# aop.net
KiCad netlist of a schematic drawn in EAGLE
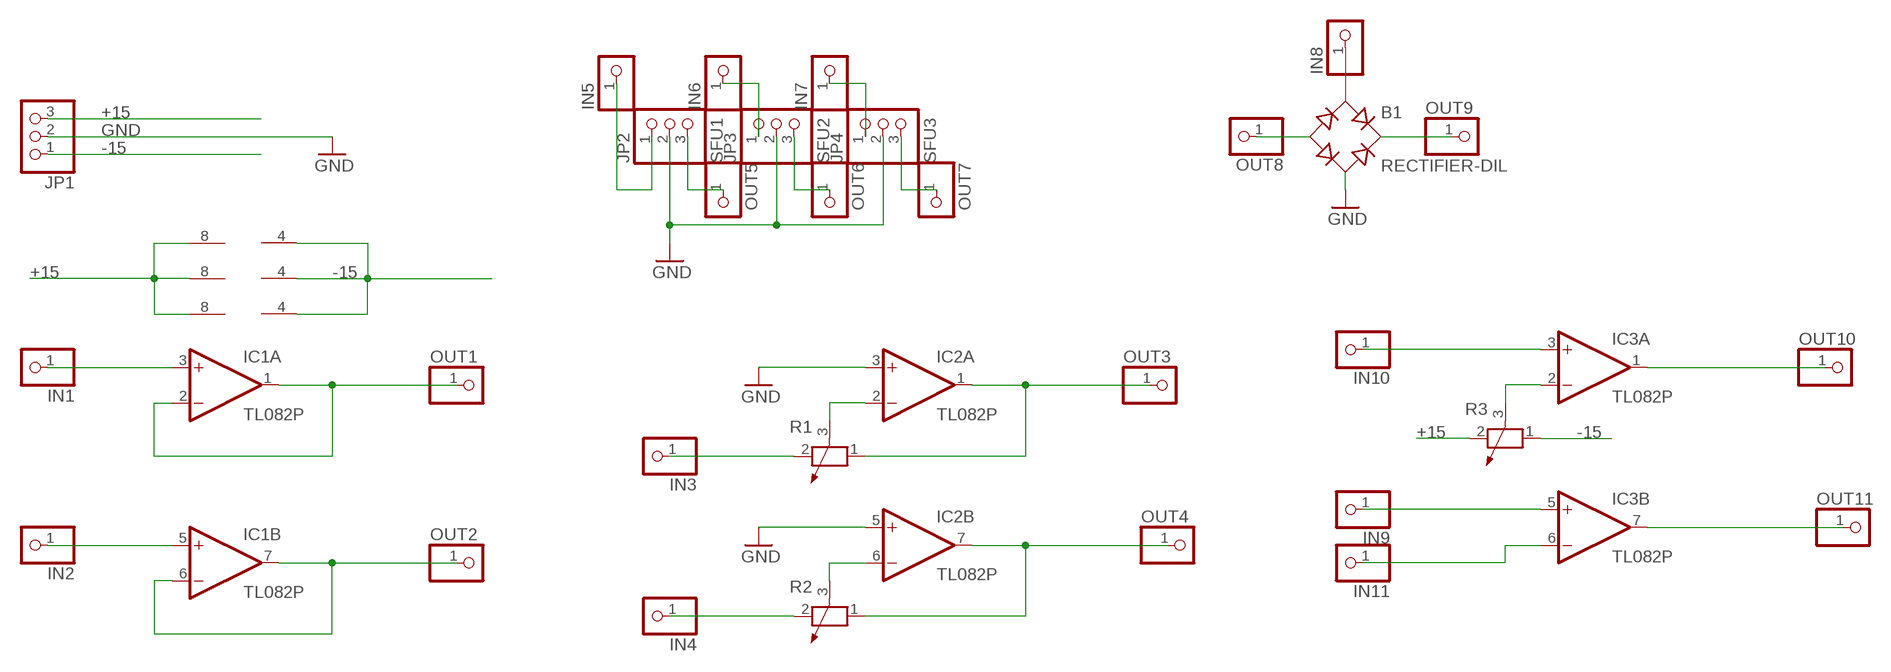
[diagram p0: schematic, sheet 1]

(export (version "E")
  (design (tool "Eeschema 10.0.6"))
  (components
    (comp (ref "B1")
      (value "RECTIFIER-DIL")
      (footprint "eagle-import:B-DIL")
      (libsource (lib "eagle-import") (part "RECTIFIER-DIL"))
    )
    (comp (ref "IC1")
      (value "TL082P")
      (footprint "eagle-import:DIL08")
      (libsource (lib "eagle-import") (part "TL082P"))
    )
    (comp (ref "IC2")
      (value "TL082P")
      (footprint "eagle-import:DIL08")
      (libsource (lib "eagle-import") (part "TL082P"))
    )
    (comp (ref "IC3")
      (value "TL082P")
      (footprint "eagle-import:DIL08")
      (libsource (lib "eagle-import") (part "TL082P"))
    )
    (comp (ref "IN1")
      (value "PINHD-1X1")
      (footprint "eagle-import:1X01")
      (libsource (lib "eagle-import") (part "PINHD-1X1"))
    )
    (comp (ref "IN2")
      (value "PINHD-1X1")
      (footprint "eagle-import:1X01")
      (libsource (lib "eagle-import") (part "PINHD-1X1"))
    )
    (comp (ref "IN3")
      (value "PINHD-1X1")
      (footprint "eagle-import:1X01")
      (libsource (lib "eagle-import") (part "PINHD-1X1"))
    )
    (comp (ref "IN4")
      (value "PINHD-1X1")
      (footprint "eagle-import:1X01")
      (libsource (lib "eagle-import") (part "PINHD-1X1"))
    )
    (comp (ref "IN5")
      (value "PINHD-1X1")
      (footprint "eagle-import:1X01")
      (libsource (lib "eagle-import") (part "PINHD-1X1"))
    )
    (comp (ref "IN6")
      (value "PINHD-1X1")
      (footprint "eagle-import:1X01")
      (libsource (lib "eagle-import") (part "PINHD-1X1"))
    )
    (comp (ref "IN7")
      (value "PINHD-1X1")
      (footprint "eagle-import:1X01")
      (libsource (lib "eagle-import") (part "PINHD-1X1"))
    )
    (comp (ref "IN8")
      (value "PINHD-1X1")
      (footprint "eagle-import:1X01")
      (libsource (lib "eagle-import") (part "PINHD-1X1"))
    )
    (comp (ref "IN9")
      (value "PINHD-1X1")
      (footprint "eagle-import:1X01")
      (libsource (lib "eagle-import") (part "PINHD-1X1"))
    )
    (comp (ref "IN10")
      (value "PINHD-1X1")
      (footprint "eagle-import:1X01")
      (libsource (lib "eagle-import") (part "PINHD-1X1"))
    )
    (comp (ref "IN11")
      (value "PINHD-1X1")
      (footprint "eagle-import:1X01")
      (libsource (lib "eagle-import") (part "PINHD-1X1"))
    )
    (comp (ref "JP1")
      (value "PINHD-1X3")
      (footprint "eagle-import:1X03")
      (libsource (lib "eagle-import") (part "PINHD-1X3"))
    )
    (comp (ref "JP2")
      (value "SFU1")
      (footprint "eagle-import:1X03")
      (libsource (lib "eagle-import") (part "PINHD-1X3"))
    )
    (comp (ref "JP3")
      (value "SFU2")
      (footprint "eagle-import:1X03")
      (libsource (lib "eagle-import") (part "PINHD-1X3"))
    )
    (comp (ref "JP4")
      (value "SFU3")
      (footprint "eagle-import:1X03")
      (libsource (lib "eagle-import") (part "PINHD-1X3"))
    )
    (comp (ref "OUT1")
      (value "PINHD-1X1")
      (footprint "eagle-import:1X01")
      (libsource (lib "eagle-import") (part "PINHD-1X1"))
    )
    (comp (ref "OUT2")
      (value "PINHD-1X1")
      (footprint "eagle-import:1X01")
      (libsource (lib "eagle-import") (part "PINHD-1X1"))
    )
    (comp (ref "OUT3")
      (value "PINHD-1X1")
      (footprint "eagle-import:1X01")
      (libsource (lib "eagle-import") (part "PINHD-1X1"))
    )
    (comp (ref "OUT4")
      (value "PINHD-1X1")
      (footprint "eagle-import:1X01")
      (libsource (lib "eagle-import") (part "PINHD-1X1"))
    )
    (comp (ref "OUT5")
      (value "PINHD-1X1")
      (footprint "eagle-import:1X01")
      (libsource (lib "eagle-import") (part "PINHD-1X1"))
    )
    (comp (ref "OUT6")
      (value "PINHD-1X1")
      (footprint "eagle-import:1X01")
      (libsource (lib "eagle-import") (part "PINHD-1X1"))
    )
    (comp (ref "OUT7")
      (value "PINHD-1X1")
      (footprint "eagle-import:1X01")
      (libsource (lib "eagle-import") (part "PINHD-1X1"))
    )
    (comp (ref "OUT8")
      (value "PINHD-1X1")
      (footprint "eagle-import:1X01")
      (libsource (lib "eagle-import") (part "PINHD-1X1"))
    )
    (comp (ref "OUT9")
      (value "PINHD-1X1")
      (footprint "eagle-import:1X01")
      (libsource (lib "eagle-import") (part "PINHD-1X1"))
    )
    (comp (ref "OUT10")
      (value "PINHD-1X1")
      (footprint "eagle-import:1X01")
      (libsource (lib "eagle-import") (part "PINHD-1X1"))
    )
    (comp (ref "OUT11")
      (value "PINHD-1X1")
      (footprint "eagle-import:1X01")
      (libsource (lib "eagle-import") (part "PINHD-1X1"))
    )
    (comp (ref "R1")
      (value "POTENTIOMETER_PT-10")
      (footprint "eagle-import:PT-10")
      (libsource (lib "eagle-import") (part "POTENTIOMETER_PT-10"))
    )
    (comp (ref "R2")
      (value "POTENTIOMETER_PT-10")
      (footprint "eagle-import:PT-10")
      (libsource (lib "eagle-import") (part "POTENTIOMETER_PT-10"))
    )
    (comp (ref "R3")
      (value "POTENTIOMETER_PT-10")
      (footprint "eagle-import:PT-10")
      (libsource (lib "eagle-import") (part "POTENTIOMETER_PT-10"))
    )
  )
  (nets
    (net (code "1") (name "/+15") (class "Default")
      (node (ref "IC1") (pin "8") (pinfunction "V+_8") (pintype "power_in"))
      (node (ref "IC2") (pin "8") (pinfunction "V+_8") (pintype "power_in"))
      (node (ref "IC3") (pin "8") (pinfunction "V+_8") (pintype "power_in"))
      (node (ref "JP1") (pin "3") (pinfunction "3_3") (pintype "passive"))
      (node (ref "R3") (pin "2") (pinfunction "2_2") (pintype "passive"))
    )
    (net (code "2") (name "/-15") (class "Default")
      (node (ref "IC1") (pin "4") (pinfunction "V-_4") (pintype "power_in"))
      (node (ref "IC2") (pin "4") (pinfunction "V-_4") (pintype "power_in"))
      (node (ref "IC3") (pin "4") (pinfunction "V-_4") (pintype "power_in"))
      (node (ref "JP1") (pin "1") (pinfunction "1_1") (pintype "passive"))
      (node (ref "R3") (pin "1") (pinfunction "1_1") (pintype "passive"))
    )
    (net (code "3") (name "GND") (class "Default")
      (node (ref "B1") (pin "AC2") (pinfunction "AC2_AC2") (pintype "passive"))
      (node (ref "IC2") (pin "3") (pinfunction "+IN_3") (pintype "input"))
      (node (ref "IC2") (pin "5") (pinfunction "+IN_5") (pintype "input"))
      (node (ref "JP1") (pin "2") (pinfunction "2_2") (pintype "passive"))
      (node (ref "JP2") (pin "2") (pinfunction "2_2") (pintype "passive"))
      (node (ref "JP3") (pin "2") (pinfunction "2_2") (pintype "passive"))
      (node (ref "JP4") (pin "2") (pinfunction "2_2") (pintype "passive"))
    )
    (net (code "4") (name "Net-(B1-Pad+)") (class "Default")
      (node (ref "B1") (pin "+") (pinfunction "+_+") (pintype "passive"))
      (node (ref "OUT9") (pin "1") (pinfunction "1_1") (pintype "passive"))
    )
    (net (code "5") (name "Net-(B1-Pad-)") (class "Default")
      (node (ref "B1") (pin "-") (pinfunction "-_-") (pintype "passive"))
      (node (ref "OUT8") (pin "1") (pinfunction "1_1") (pintype "passive"))
    )
    (net (code "6") (name "Net-(B1-PadAC1)") (class "Default")
      (node (ref "B1") (pin "AC1") (pinfunction "AC1_AC1") (pintype "passive"))
      (node (ref "IN8") (pin "1") (pinfunction "1_1") (pintype "passive"))
    )
    (net (code "7") (name "Net-(IC1A-+IN)") (class "Default")
      (node (ref "IC1") (pin "3") (pinfunction "+IN_3") (pintype "input"))
      (node (ref "IN1") (pin "1") (pinfunction "1_1") (pintype "passive"))
    )
    (net (code "8") (name "Net-(IC1A--IN)") (class "Default")
      (node (ref "IC1") (pin "1") (pinfunction "OUT_1") (pintype "output"))
      (node (ref "IC1") (pin "2") (pinfunction "-IN_2") (pintype "input"))
      (node (ref "OUT1") (pin "1") (pinfunction "1_1") (pintype "passive"))
    )
    (net (code "9") (name "Net-(IC1B-+IN)") (class "Default")
      (node (ref "IC1") (pin "5") (pinfunction "+IN_5") (pintype "input"))
      (node (ref "IN2") (pin "1") (pinfunction "1_1") (pintype "passive"))
    )
    (net (code "10") (name "Net-(IC1B--IN)") (class "Default")
      (node (ref "IC1") (pin "6") (pinfunction "-IN_6") (pintype "input"))
      (node (ref "IC1") (pin "7") (pinfunction "OUT_7") (pintype "output"))
      (node (ref "OUT2") (pin "1") (pinfunction "1_1") (pintype "passive"))
    )
    (net (code "11") (name "Net-(IC2A--IN)") (class "Default")
      (node (ref "IC2") (pin "2") (pinfunction "-IN_2") (pintype "input"))
      (node (ref "R1") (pin "3") (pinfunction "3_3") (pintype "passive"))
    )
    (net (code "12") (name "Net-(IC2A-OUT)") (class "Default")
      (node (ref "IC2") (pin "1") (pinfunction "OUT_1") (pintype "output"))
      (node (ref "OUT3") (pin "1") (pinfunction "1_1") (pintype "passive"))
      (node (ref "R1") (pin "1") (pinfunction "1_1") (pintype "passive"))
    )
    (net (code "13") (name "Net-(IC2B--IN)") (class "Default")
      (node (ref "IC2") (pin "6") (pinfunction "-IN_6") (pintype "input"))
      (node (ref "R2") (pin "3") (pinfunction "3_3") (pintype "passive"))
    )
    (net (code "14") (name "Net-(IC2B-OUT)") (class "Default")
      (node (ref "IC2") (pin "7") (pinfunction "OUT_7") (pintype "output"))
      (node (ref "OUT4") (pin "1") (pinfunction "1_1") (pintype "passive"))
      (node (ref "R2") (pin "1") (pinfunction "1_1") (pintype "passive"))
    )
    (net (code "15") (name "Net-(IC3A-+IN)") (class "Default")
      (node (ref "IC3") (pin "3") (pinfunction "+IN_3") (pintype "input"))
      (node (ref "IN10") (pin "1") (pinfunction "1_1") (pintype "passive"))
    )
    (net (code "16") (name "Net-(IC3A--IN)") (class "Default")
      (node (ref "IC3") (pin "2") (pinfunction "-IN_2") (pintype "input"))
      (node (ref "R3") (pin "3") (pinfunction "3_3") (pintype "passive"))
    )
    (net (code "17") (name "Net-(IC3A-OUT)") (class "Default")
      (node (ref "IC3") (pin "1") (pinfunction "OUT_1") (pintype "output"))
      (node (ref "OUT10") (pin "1") (pinfunction "1_1") (pintype "passive"))
    )
    (net (code "18") (name "Net-(IC3B-+IN)") (class "Default")
      (node (ref "IC3") (pin "5") (pinfunction "+IN_5") (pintype "input"))
      (node (ref "IN9") (pin "1") (pinfunction "1_1") (pintype "passive"))
    )
    (net (code "19") (name "Net-(IC3B--IN)") (class "Default")
      (node (ref "IC3") (pin "6") (pinfunction "-IN_6") (pintype "input"))
      (node (ref "IN11") (pin "1") (pinfunction "1_1") (pintype "passive"))
    )
    (net (code "20") (name "Net-(IC3B-OUT)") (class "Default")
      (node (ref "IC3") (pin "7") (pinfunction "OUT_7") (pintype "output"))
      (node (ref "OUT11") (pin "1") (pinfunction "1_1") (pintype "passive"))
    )
    (net (code "21") (name "Net-(IN3-Pad1)") (class "Default")
      (node (ref "IN3") (pin "1") (pinfunction "1_1") (pintype "passive"))
      (node (ref "R1") (pin "2") (pinfunction "2_2") (pintype "passive"))
    )
    (net (code "22") (name "Net-(IN4-Pad1)") (class "Default")
      (node (ref "IN4") (pin "1") (pinfunction "1_1") (pintype "passive"))
      (node (ref "R2") (pin "2") (pinfunction "2_2") (pintype "passive"))
    )
    (net (code "23") (name "Net-(IN5-Pad1)") (class "Default")
      (node (ref "IN5") (pin "1") (pinfunction "1_1") (pintype "passive"))
      (node (ref "JP2") (pin "1") (pinfunction "1_1") (pintype "passive"))
    )
    (net (code "24") (name "Net-(IN6-Pad1)") (class "Default")
      (node (ref "IN6") (pin "1") (pinfunction "1_1") (pintype "passive"))
      (node (ref "JP3") (pin "1") (pinfunction "1_1") (pintype "passive"))
    )
    (net (code "25") (name "Net-(IN7-Pad1)") (class "Default")
      (node (ref "IN7") (pin "1") (pinfunction "1_1") (pintype "passive"))
      (node (ref "JP4") (pin "1") (pinfunction "1_1") (pintype "passive"))
    )
    (net (code "26") (name "Net-(JP2-Pad3)") (class "Default")
      (node (ref "JP2") (pin "3") (pinfunction "3_3") (pintype "passive"))
      (node (ref "OUT5") (pin "1") (pinfunction "1_1") (pintype "passive"))
    )
    (net (code "27") (name "Net-(JP3-Pad3)") (class "Default")
      (node (ref "JP3") (pin "3") (pinfunction "3_3") (pintype "passive"))
      (node (ref "OUT6") (pin "1") (pinfunction "1_1") (pintype "passive"))
    )
    (net (code "28") (name "Net-(JP4-Pad3)") (class "Default")
      (node (ref "JP4") (pin "3") (pinfunction "3_3") (pintype "passive"))
      (node (ref "OUT7") (pin "1") (pinfunction "1_1") (pintype "passive"))
    )
  )
)
